# SD_Card_Reader.net
KiCad netlist of a schematic drawn in Altium Designer
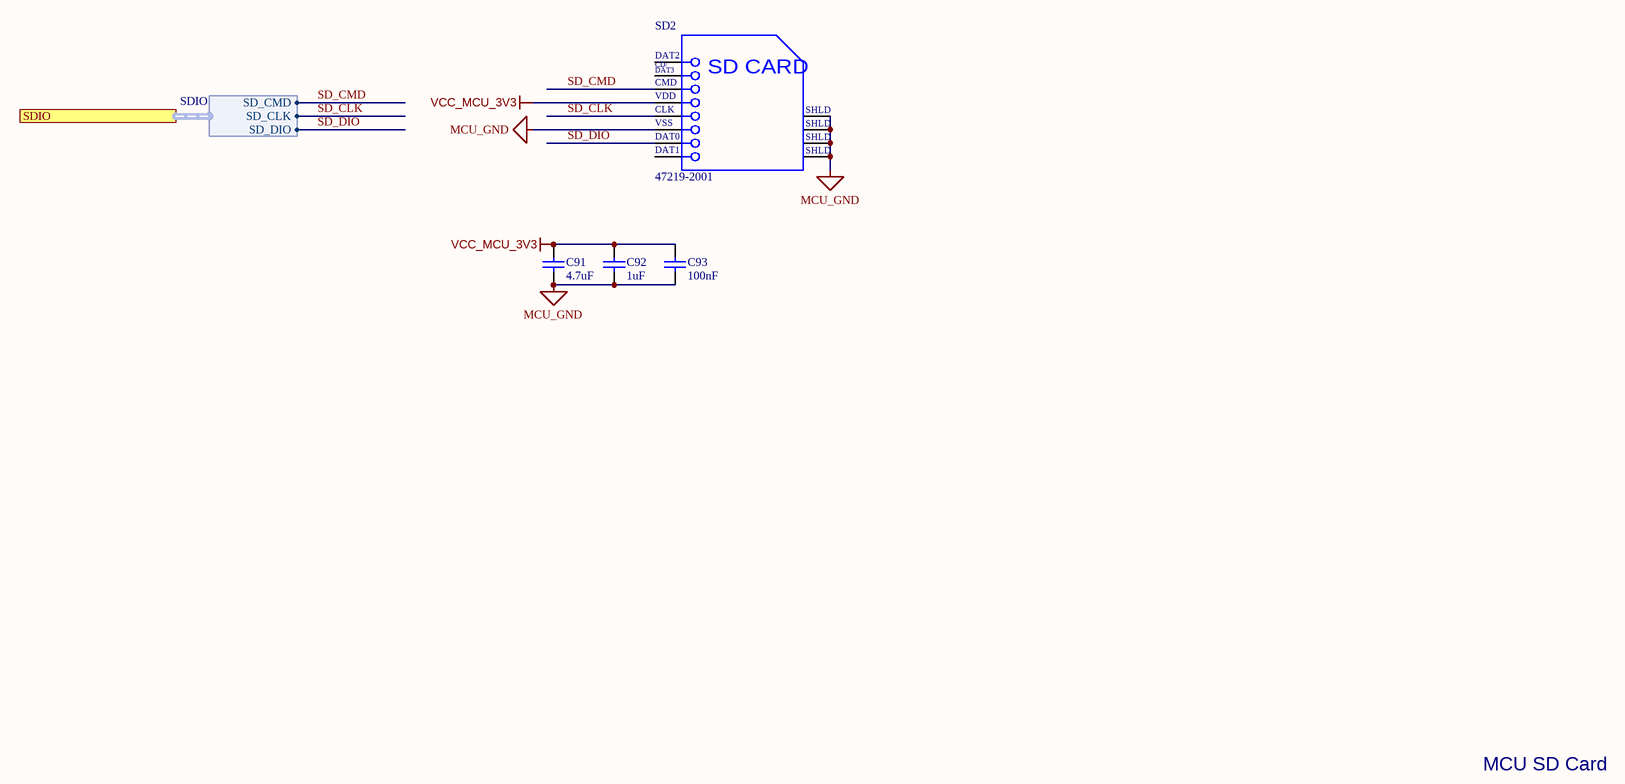
[diagram p0: SD_Card_Reader.SchDoc]

(export (version "E")
  (design (tool "Eeschema 10.0.6"))
  (components
    (comp (ref "C91")
      (value "4.7uF")
      (footprint "0603_C")
      (description "Chip capacitors")
      (fields
        (field (name "MANUFACTURER") "Samsung Electro-Mechanics")
        (field (name "PARTNUMBER") "CL10A475KO8NNNC")
      )
      (libsource (lib "Cap") (part "0603 4.7uF (475) 10% 16V"))
    )
    (comp (ref "C92")
      (value "1uF")
      (footprint "0603_C")
      (description "Chip capacitors")
      (fields
        (field (name "MANUFACTURER") "Samsung Electro-Mechanics")
        (field (name "MANUFACTURER PART NUMBER") "CL10A105KB8NNNC")
      )
      (libsource (lib "Cap") (part "0603 1uF (105) 10% 50V"))
    )
    (comp (ref "C93")
      (value "100nF")
      (footprint "0603_C")
      (description "Chip capacitors")
      (fields
        (field (name "MANUFACTURER") "YAGEO")
        (field (name "MANUFACTURER PART NUMBER") "CC0603KRX7R9BB104")
      )
      (libsource (lib "Cap") (part "0603 100nF (104) 10% 50V"))
    )
    (comp (ref "SD2")
      (value "47219-2001")
      (footprint "472192001")
      (description "Conn Micro SD Card SKT 8 POS 1.1mm Solder RA SMD 0.5A/Contact Embossed T/R")
      (fields (field (name "MANUFACTURER") "Molex"))
      (libsource (lib "Sienci_Labs") (part "47219-2001"))
    )
  )
  (nets
    (net (code "2") (name "/SD_CLK") (class "Default")
      (node (ref "SD2") (pin "5") (pinfunction "CLK_5") (pintype "passive"))
    )
    (net (code "3") (name "/SD_CMD") (class "Default")
      (node (ref "SD2") (pin "3") (pinfunction "CMD_3") (pintype "passive"))
    )
    (net (code "4") (name "/SD_DIO") (class "Default")
      (node (ref "SD2") (pin "7") (pinfunction "DAT0_7") (pintype "passive"))
    )
    (net (code "6") (name "MCU_GND") (class "Default")
      (node (ref "C91") (pin "1") (pinfunction "1_1") (pintype "passive"))
      (node (ref "C92") (pin "1") (pinfunction "1_1") (pintype "passive"))
      (node (ref "C93") (pin "1") (pinfunction "1_1") (pintype "passive"))
      (node (ref "SD2") (pin "10") (pinfunction "SHLD_10") (pintype "passive"))
      (node (ref "SD2") (pin "11") (pinfunction "SHLD_11") (pintype "passive"))
      (node (ref "SD2") (pin "12") (pinfunction "SHLD_12") (pintype "passive"))
      (node (ref "SD2") (pin "6") (pinfunction "VSS_6") (pintype "passive"))
      (node (ref "SD2") (pin "9") (pinfunction "SHLD_9") (pintype "passive"))
    )
    (net (code "7") (name "VCC_MCU_3V3") (class "Default")
      (node (ref "C91") (pin "2") (pinfunction "2_2") (pintype "passive"))
      (node (ref "C92") (pin "2") (pinfunction "2_2") (pintype "passive"))
      (node (ref "C93") (pin "2") (pinfunction "2_2") (pintype "passive"))
      (node (ref "SD2") (pin "4") (pinfunction "VDD_4") (pintype "passive"))
    )
    (net (code "8") (name "unconnected-(SD2-CD{slash}DAT3-Pad2)") (class "Default")
      (node (ref "SD2") (pin "2") (pinfunction "CD/DAT3_2") (pintype "passive"))
    )
    (net (code "9") (name "unconnected-(SD2-DAT1-Pad8)") (class "Default")
      (node (ref "SD2") (pin "8") (pinfunction "DAT1_8") (pintype "passive"))
    )
    (net (code "10") (name "unconnected-(SD2-DAT2-Pad1)") (class "Default")
      (node (ref "SD2") (pin "1") (pinfunction "DAT2_1") (pintype "passive"))
    )
  )
)
